# Power-Supply.net
KiCad netlist of a schematic drawn in Altium Designer
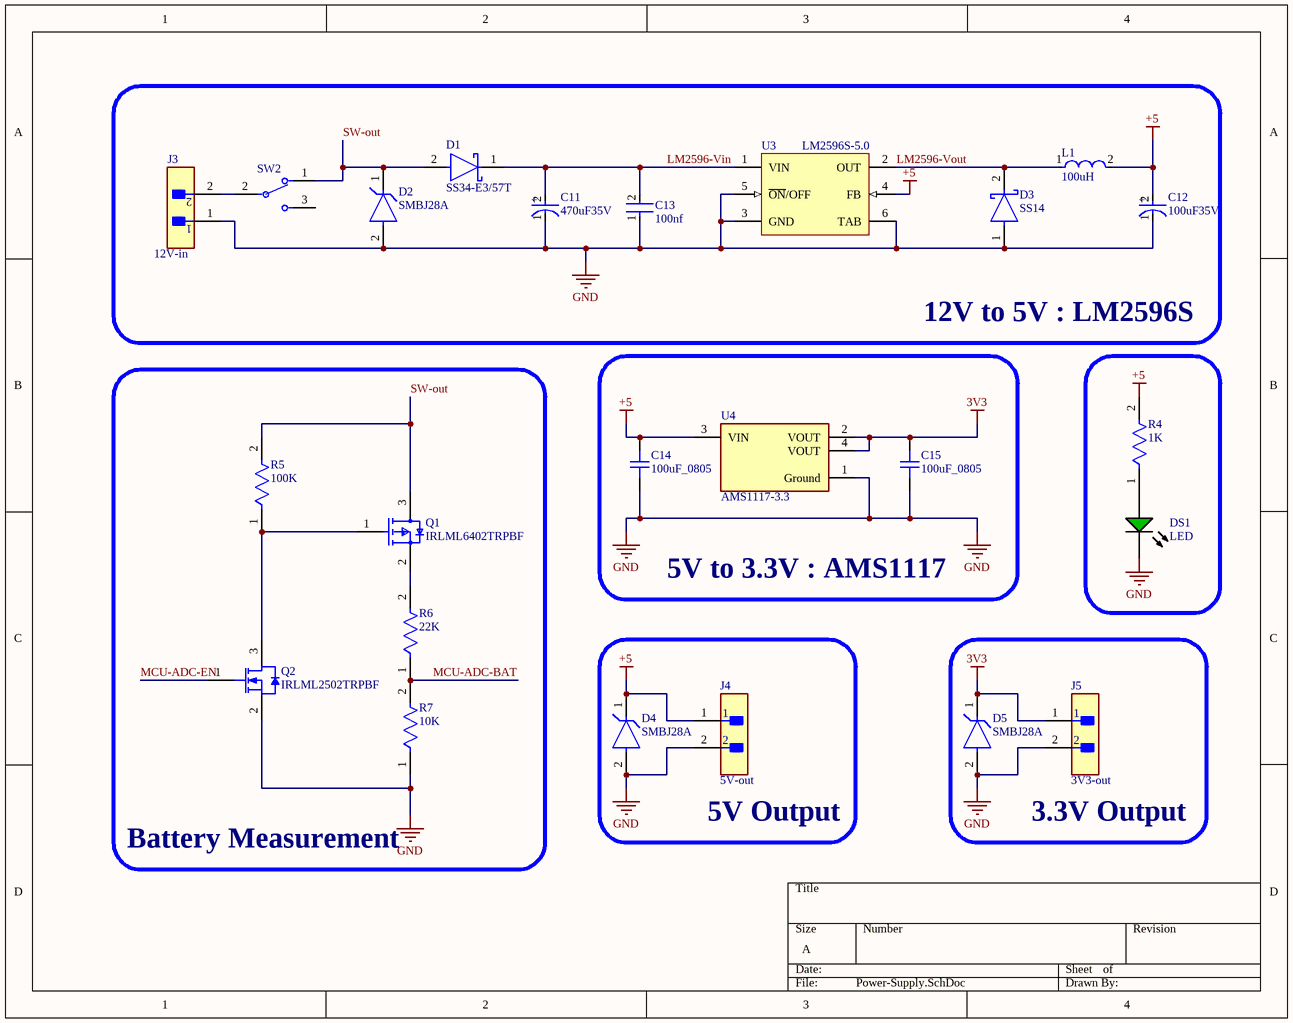
[diagram p0: Power-Supply.SchDoc]

(export (version "E")
  (design (tool "Eeschema 10.0.6"))
  (components
    (comp (ref "C11")
      (value "470uF35V")
      (footprint "FP-RAD-TH-D_10_0_5-L_16_1-MFG")
      (description "Aluminum Electrolytic Capacitors (Radial Lead Type) AEC-Q200 Qualified 470uF ±20% 35V")
      (fields (field (name "TOLERANCE") "20%"))
      (libsource (lib "Altium Content Vault") (part "a00bbbee19879c290e62620ae7e47b1"))
    )
    (comp (ref "C12")
      (value "100uF35V")
      (footprint "FP-RAD-TH-D_10_0_5-L_16_1-MFG")
      (description "Aluminum Electrolytic Capacitors (Radial Lead Type) AEC-Q200 Qualified 470uF ±20% 35V")
      (fields (field (name "TOLERANCE") "20%"))
      (libsource (lib "Altium Content Vault") (part "a00bbbee19879c290e62620ae7e47b1"))
    )
    (comp (ref "C13")
      (value "100nf")
      (footprint "FP-CC0805-0_85-MFG")
      (description "CAP CER 0.1UF 50V X7R 0805")
      (fields (field (name "TOLERANCE") "0.1") (field (name "MANUFACTURER PART NUMBER") "CC0805KRX7R9BB104"))
      (libsource (lib "Altium Content Vault") (part "11868f565c42a9108669ba33697ecf6"))
    )
    (comp (ref "C14")
      (value "100uF_0805")
      (footprint "CAP_0805")
      (description "Capacitor SMD 0805 10V")
      (libsource (lib "Schematic-Lib-PhilsLab") (part "CAP_0805_10V"))
    )
    (comp (ref "C15")
      (value "100uF_0805")
      (footprint "CAP_0805")
      (description "Capacitor SMD 0805 10V")
      (libsource (lib "Schematic-Lib-PhilsLab") (part "CAP_0805_10V"))
    )
    (comp (ref "D1")
      (value "SS34-E3/57T")
      (footprint "FP-95402-MFG")
      (description "DIODE SCHOTTKY 40V 3A DO214AB")
      (fields
        (field (name "MANUFACTURER") "Vishay")
        (field (name "OCTOPART") "https://octopart.com/ss34-e3%2F57t-vishay-39552907")
      )
      (libsource (lib "Altium Content Vault") (part "1d6ec82d83fb6aee721767c19dac4b9"))
    )
    (comp (ref "D2")
      (value "SMBJ28A")
      (footprint "FP-SMBJ-MFG")
      (description "TVS DIODE 28V 45.4V DO214AA")
      (fields
        (field (name "MANUFACTURER") "Littelfuse Inc")
        (field (name "OCTOPART") "https://octopart.com/smbj28a-littelfuse-350790")
      )
      (libsource (lib "Altium Content Vault") (part "f813f71cba58e380607f5dd3caf9714"))
    )
    (comp (ref "D3")
      (value "SS14")
      (footprint "FP-403AE-MFG")
      (description "DIODE SCHOTTKY 40V 1A SMA")
      (fields
        (field (name "MANUFACTURER") "ON Semiconductor")
        (field (name "OCTOPART") "https://octopart.com/ss14-on+semiconductor-29205033")
      )
      (libsource (lib "Altium Content Vault") (part "360ad2f4ac25a952324d13796385471"))
    )
    (comp (ref "D4")
      (value "SMBJ28A")
      (footprint "FP-SMBJ-MFG")
      (description "TVS DIODE 28V 45.4V DO214AA")
      (fields
        (field (name "MANUFACTURER") "Littelfuse Inc")
        (field (name "OCTOPART") "https://octopart.com/smbj28a-littelfuse-350790")
      )
      (libsource (lib "Altium Content Vault") (part "f813f71cba58e380607f5dd3caf9714"))
    )
    (comp (ref "D5")
      (value "SMBJ28A")
      (footprint "FP-SMBJ-MFG")
      (description "TVS DIODE 28V 45.4V DO214AA")
      (fields
        (field (name "MANUFACTURER") "Littelfuse Inc")
        (field (name "OCTOPART") "https://octopart.com/smbj28a-littelfuse-350790")
      )
      (libsource (lib "Altium Content Vault") (part "f813f71cba58e380607f5dd3caf9714"))
    )
    (comp (ref "DS1")
      (value "LED")
      (footprint "AVAG-HSMX-C170_V")
      (description "Chip LED, Green, 2.2 V, -40 to 85 degC, 2-Pin SMD, Pb-Free, Tape and Reel")
      (fields (field (name "MANUFACTURER") "Avago"))
      (libsource (lib "Altium Content Vault") (part "LED_GREEN_A1K2-2"))
    )
    (comp (ref "J3")
      (value "12V-in")
      (footprint "FP-B2B-XH-A_LF_SN-MFG")
      (description "CONN HEADER VERT 2POS 2.5MM")
      (libsource (lib "Altium Content Vault") (part "3bc925449376181038e59eaffc5286c"))
    )
    (comp (ref "J4")
      (value "5V-out")
      (footprint "FP-B2B-XH-A_LF_SN-MFG")
      (description "CONN HEADER VERT 2POS 2.5MM")
      (libsource (lib "") (part "3bc925449376181038e59eaffc5286c_1"))
    )
    (comp (ref "J5")
      (value "3V3-out")
      (footprint "FP-B2B-XH-A_LF_SN-MFG")
      (description "CONN HEADER VERT 2POS 2.5MM")
      (libsource (lib "") (part "3bc925449376181038e59eaffc5286c_1"))
    )
    (comp (ref "L1")
      (value "100uH")
      (footprint "FP-B82464G4-MFG")
      (description "FIXED IND 68UH 1.3A 130 MOHM SMD")
      (fields
        (field (name "OCTOPART") "https://octopart.com/b82464g4683m000-epcos-23277316")
        (field (name "MANUFACTURER") "EPCOS")
      )
      (libsource (lib "Altium Content Vault") (part "725321dda6339637d4d059423bc1c3c"))
    )
    (comp (ref "Q1")
      (value "IRLML6402TRPBF")
      (footprint "FP-Micro3-MFG")
      (description "MOSFET P-CH 20V 3.7A SOT-23")
      (fields
        (field (name "OCTOPART") "https://octopart.com/irlml6402trpbf-infineon-65874989")
        (field (name "MANUFACTURER") "Infineon")
      )
      (libsource (lib "Altium Content Vault") (part "566027c8dc92b5207d53ac25ab3eb60"))
    )
    (comp (ref "Q2")
      (value "IRLML2502TRPBF")
      (footprint "INTR-SOT-23-3_V")
      (description "N-Channel HEXFET(R) Power MOSFET, 20 V VDS, +/- 12 V VGS, 4.2 A, 3-Pin SOT23, RoHS, Tape and Reel")
      (fields (field (name "MANUFACTURER") "International Rectifier"))
      (libsource (lib "Altium Content Vault") (part "NEMOS-GSD-3"))
    )
    (comp (ref "R4")
      (value "1K")
      (footprint "FP-CRCW0805-e3-MFG")
      (description "RES Thick Film, 100kΩ, 1%, 0.125W, 100ppm/°C, 0805")
      (fields (field (name "TOLERANCE") "1%"))
      (libsource (lib "Altium Content Vault") (part "1029c3af85768c4190bb7ad29bc67b5"))
    )
    (comp (ref "R5")
      (value "100K")
      (footprint "FP-CRCW0805-e3-MFG")
      (description "RES Thick Film, 100kΩ, 1%, 0.125W, 100ppm/°C, 0805")
      (fields (field (name "TOLERANCE") "1%"))
      (libsource (lib "Altium Content Vault") (part "1029c3af85768c4190bb7ad29bc67b5"))
    )
    (comp (ref "R6")
      (value "22K")
      (footprint "FP-CRCW0805-e3-MFG")
      (description "RES Thick Film, 100kΩ, 1%, 0.125W, 100ppm/°C, 0805")
      (fields (field (name "TOLERANCE") "1%"))
      (libsource (lib "Altium Content Vault") (part "1029c3af85768c4190bb7ad29bc67b5"))
    )
    (comp (ref "R7")
      (value "10K")
      (footprint "FP-CRCW0805-e3-MFG")
      (description "RES Thick Film, 100kΩ, 1%, 0.125W, 100ppm/°C, 0805")
      (fields (field (name "TOLERANCE") "1%"))
      (libsource (lib "Altium Content Vault") (part "1029c3af85768c4190bb7ad29bc67b5"))
    )
    (comp (ref "SW2")
      (value "JS102011SCQN")
      (footprint "FP-JS102011SCQN-MFG")
      (description "SWITCH SLIDE SPDT 300MA 6V")
      (libsource (lib "Altium Content Vault") (part "39e195cbbadc85d1df0d7eb6847d379"))
    )
    (comp (ref "U3")
      (value "LM2596S-5.0")
      (footprint "KTT0005B_M")
      (description "SIMPLE SWITCHER® Power Converter 150 KHz 3A Step-Down Voltage Regulator, 5-pin TO-263, Pb-Free")
      (fields (field (name "MANUFACTURER") "Texas Instruments"))
      (libsource (lib "Altium Content Vault") (part "PM-REG-LM2575HVS-12"))
    )
    (comp (ref "U4")
      (value "AMS1117-3.3")
      (footprint "FP-AMS1117-IPC_C")
      (description "LDO Voltage Regulators 1A, 3.3V")
      (fields
        (field (name "OCTOPART") "https://octopart.com/ams1117-3.3-advanced+monolithic+systems-25899300")
        (field (name "MANUFACTURER") "Advanced Monolithic Systems")
      )
      (libsource (lib "Altium Content Vault") (part "8bdbb5f8e77002000e30dd2845d0354"))
    )
  )
  (nets
    (net (code "1") (name "+5") (class "Default")
      (node (ref "C12") (pin "2") (pinfunction "A_2") (pintype "passive"))
      (node (ref "C14") (pin "2") (pinfunction "2_2") (pintype "passive"))
      (node (ref "D4") (pin "1") (pinfunction "C_1") (pintype "passive"))
      (node (ref "J4") (pin "1") (pinfunction "1_1") (pintype "passive"))
      (node (ref "L1") (pin "2") (pinfunction "2_2") (pintype "passive"))
      (node (ref "R4") (pin "2") (pinfunction "2_2") (pintype "passive"))
      (node (ref "U3") (pin "4") (pinfunction "FB_4") (pintype "input"))
      (node (ref "U4") (pin "3") (pinfunction "VIN_3") (pintype "power_in"))
    )
    (net (code "2") (name "/LM2596-Vin") (class "Default")
      (node (ref "C11") (pin "2") (pinfunction "A_2") (pintype "passive"))
      (node (ref "C13") (pin "2") (pinfunction "2_2") (pintype "passive"))
      (node (ref "D1") (pin "1") (pinfunction "C_1") (pintype "passive"))
      (node (ref "U3") (pin "1") (pinfunction "VIN_1") (pintype "power_in"))
    )
    (net (code "3") (name "/LM2596-Vout") (class "Default")
      (node (ref "D3") (pin "2") (pinfunction "C_2") (pintype "passive"))
      (node (ref "L1") (pin "1") (pinfunction "1_1") (pintype "passive"))
      (node (ref "U3") (pin "2") (pinfunction "OUT_2") (pintype "power_in"))
    )
    (net (code "4") (name "/MCU-ADC-BAT") (class "Default")
      (node (ref "R6") (pin "1") (pinfunction "1_1") (pintype "passive"))
      (node (ref "R7") (pin "2") (pinfunction "2_2") (pintype "passive"))
    )
    (net (code "5") (name "/MCU-ADC-EN") (class "Default")
      (node (ref "Q2") (pin "1") (pinfunction "G_1") (pintype "passive"))
    )
    (net (code "6") (name "/SW-out") (class "Default")
      (node (ref "D1") (pin "2") (pinfunction "A_2") (pintype "passive"))
      (node (ref "D2") (pin "1") (pinfunction "C_1") (pintype "passive"))
      (node (ref "Q1") (pin "3") (pinfunction "D_3") (pintype "passive"))
      (node (ref "R5") (pin "2") (pinfunction "2_2") (pintype "passive"))
      (node (ref "SW2") (pin "1") (pinfunction "1_1") (pintype "passive"))
    )
    (net (code "7") (name "3V3") (class "Default")
      (node (ref "C15") (pin "2") (pinfunction "2_2") (pintype "passive"))
      (node (ref "D5") (pin "1") (pinfunction "C_1") (pintype "passive"))
      (node (ref "J5") (pin "1") (pinfunction "1_1") (pintype "passive"))
      (node (ref "U4") (pin "2") (pinfunction "VOUT_2") (pintype "passive"))
      (node (ref "U4") (pin "4") (pinfunction "VOUT_4") (pintype "passive"))
    )
    (net (code "8") (name "GND") (class "Default")
      (node (ref "C11") (pin "1") (pinfunction "C_1") (pintype "passive"))
      (node (ref "C12") (pin "1") (pinfunction "C_1") (pintype "passive"))
      (node (ref "C13") (pin "1") (pinfunction "1_1") (pintype "passive"))
      (node (ref "C14") (pin "1") (pinfunction "1_1") (pintype "passive"))
      (node (ref "C15") (pin "1") (pinfunction "1_1") (pintype "passive"))
      (node (ref "D2") (pin "2") (pinfunction "A_2") (pintype "passive"))
      (node (ref "D3") (pin "1") (pinfunction "A_1") (pintype "passive"))
      (node (ref "D4") (pin "2") (pinfunction "A_2") (pintype "passive"))
      (node (ref "D5") (pin "2") (pinfunction "A_2") (pintype "passive"))
      (node (ref "DS1") (pin "2") (pinfunction "K_2") (pintype "passive"))
      (node (ref "J3") (pin "1") (pinfunction "1_1") (pintype "passive"))
      (node (ref "J4") (pin "2") (pinfunction "2_2") (pintype "passive"))
      (node (ref "J5") (pin "2") (pinfunction "2_2") (pintype "passive"))
      (node (ref "Q2") (pin "2") (pinfunction "S_2") (pintype "passive"))
      (node (ref "R7") (pin "1") (pinfunction "1_1") (pintype "passive"))
      (node (ref "U3") (pin "3") (pinfunction "GND_3") (pintype "power_in"))
      (node (ref "U3") (pin "5") (pinfunction "~{ON}/OFF_5") (pintype "input"))
      (node (ref "U3") (pin "6") (pinfunction "TAB_6") (pintype "power_in"))
      (node (ref "U4") (pin "1") (pinfunction "Ground_1") (pintype "power_in"))
    )
    (net (code "9") (name "Net-(DS1-A)") (class "Default")
      (node (ref "DS1") (pin "1") (pinfunction "A_1") (pintype "passive"))
      (node (ref "R4") (pin "1") (pinfunction "1_1") (pintype "passive"))
    )
    (net (code "10") (name "Net-(Q1-G)") (class "Default")
      (node (ref "Q1") (pin "1") (pinfunction "G_1") (pintype "passive"))
      (node (ref "Q2") (pin "3") (pinfunction "D_3") (pintype "passive"))
      (node (ref "R5") (pin "1") (pinfunction "1_1") (pintype "passive"))
    )
    (net (code "11") (name "Net-(Q1-S)") (class "Default")
      (node (ref "Q1") (pin "2") (pinfunction "S_2") (pintype "passive"))
      (node (ref "R6") (pin "2") (pinfunction "2_2") (pintype "passive"))
    )
    (net (code "12") (name "Net-(SW2-C)") (class "Default")
      (node (ref "J3") (pin "2") (pinfunction "2_2") (pintype "passive"))
      (node (ref "SW2") (pin "2") (pinfunction "C_2") (pintype "passive"))
    )
    (net (code "13") (name "unconnected-(SW2-Pad3)") (class "Default")
      (node (ref "SW2") (pin "3") (pinfunction "3_3") (pintype "passive"))
    )
  )
)
